# working.net
KiCad netlist of a schematic drawn in EAGLE
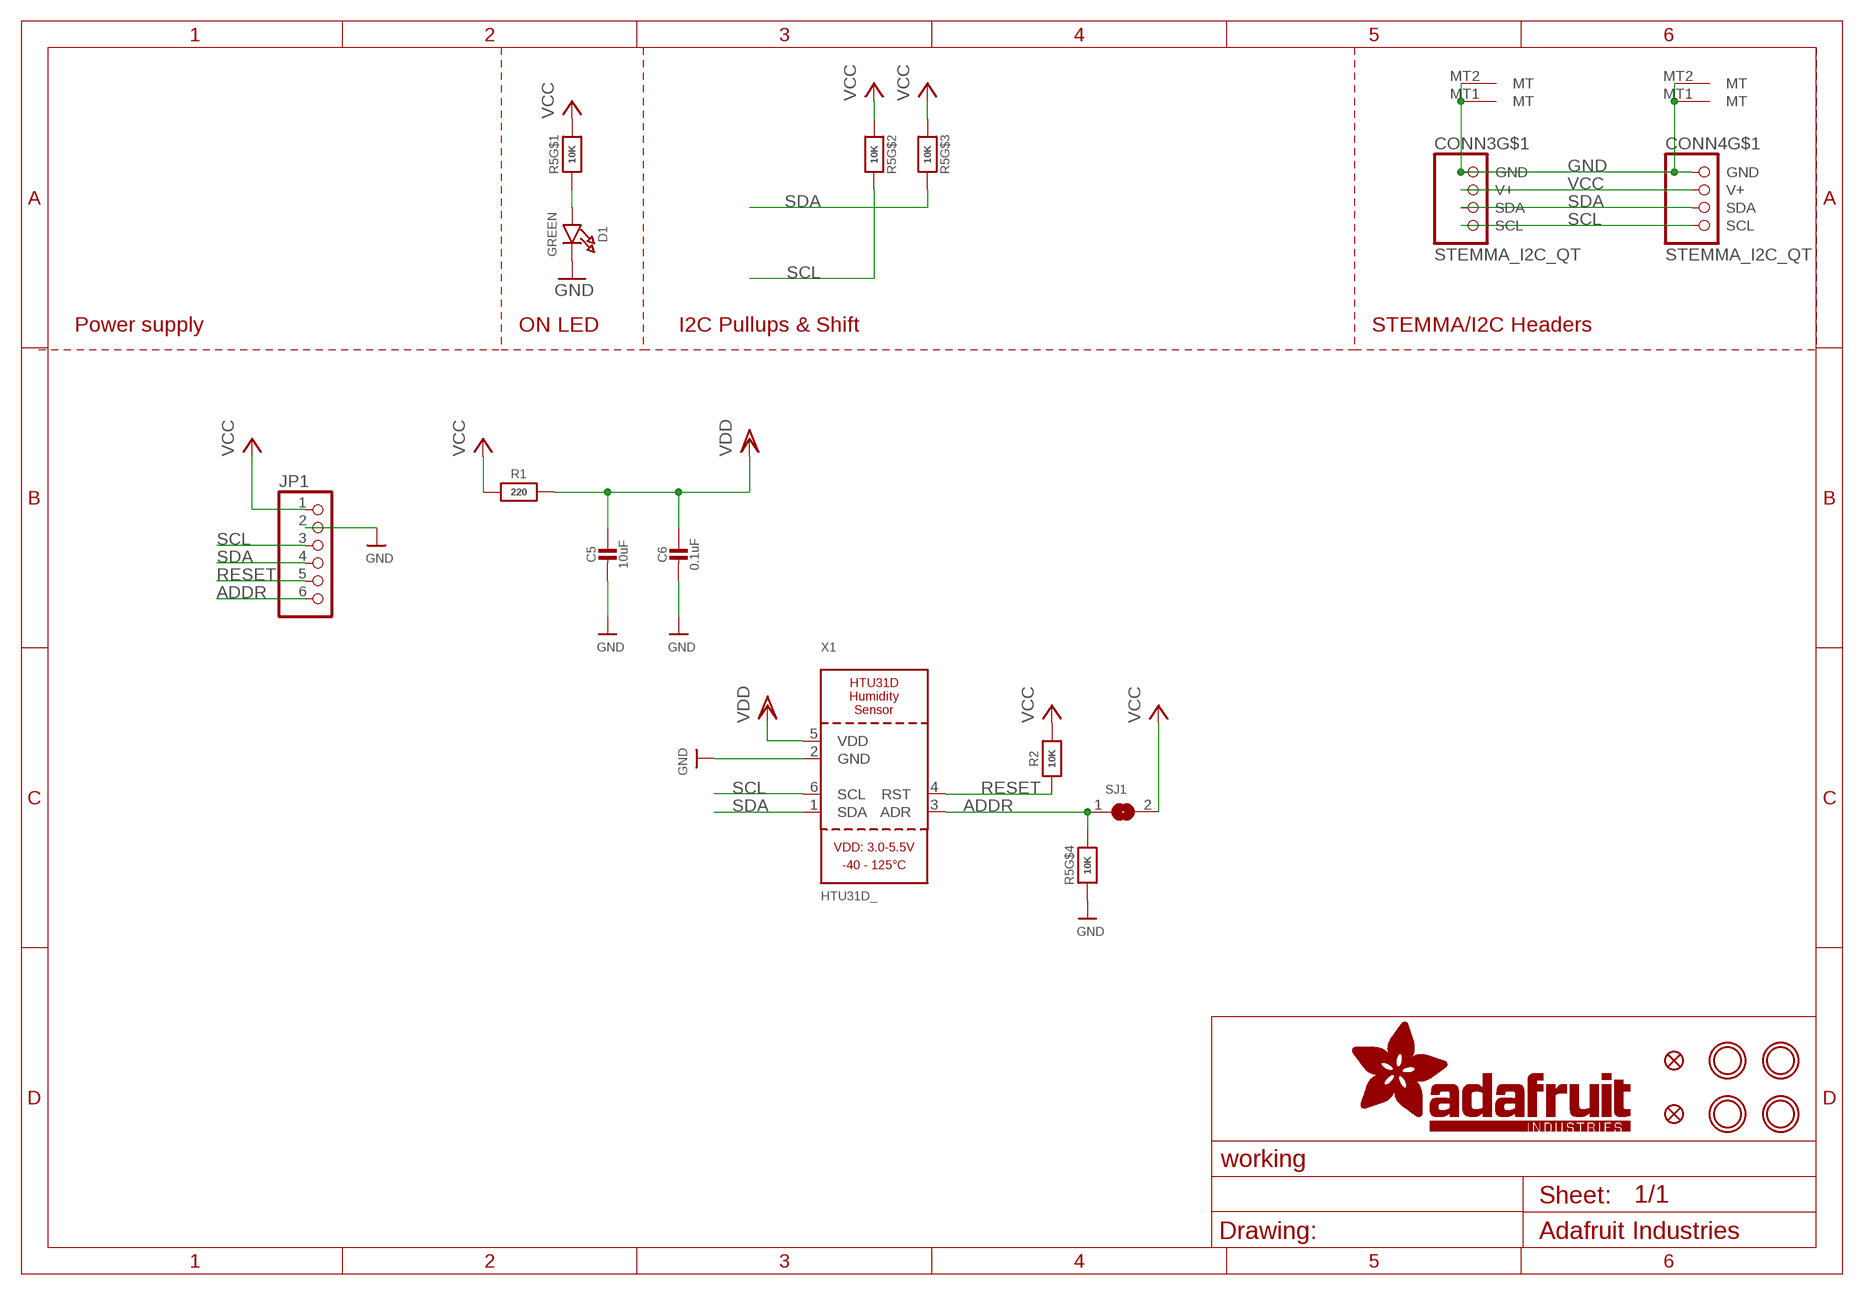
[diagram p0: schematic, sheet 1]

(export (version "E")
  (design (tool "Eeschema 10.0.6"))
  (components
    (comp (ref "C5")
      (value "10uF")
      (footprint "eagle-import:0805-NO")
      (libsource (lib "eagle-import") (part "CAP_CERAMIC0805-NOOUTLINE"))
    )
    (comp (ref "C6")
      (value "0.1uF")
      (footprint "eagle-import:0603-NO")
      (libsource (lib "eagle-import") (part "CAP_CERAMIC0603_NO"))
    )
    (comp (ref "CONN3")
      (value "STEMMA_I2C_QT")
      (footprint "eagle-import:JST_SH4")
      (libsource (lib "eagle-import") (part "STEMMA_I2C_QT"))
    )
    (comp (ref "CONN4")
      (value "STEMMA_I2C_QT")
      (footprint "eagle-import:JST_SH4")
      (libsource (lib "eagle-import") (part "STEMMA_I2C_QT"))
    )
    (comp (ref "D1")
      (value "GREEN")
      (footprint "eagle-import:CHIPLED_0603_NOOUTLINE")
      (libsource (lib "eagle-import") (part "LED0603_NOOUTLINE"))
    )
    (comp (ref "FID3")
      (value "FIDUCIAL_1MM")
      (footprint "eagle-import:FIDUCIAL_1MM")
      (libsource (lib "eagle-import") (part "FIDUCIAL_1MM"))
    )
    (comp (ref "FID4")
      (value "FIDUCIAL_1MM")
      (footprint "eagle-import:FIDUCIAL_1MM")
      (libsource (lib "eagle-import") (part "FIDUCIAL_1MM"))
    )
    (comp (ref "JP1")
      (value "HEADER-1X670MIL")
      (footprint "eagle-import:1X06_ROUND_70")
      (libsource (lib "eagle-import") (part "HEADER-1X670MIL"))
    )
    (comp (ref "R1")
      (value "220")
      (footprint "eagle-import:0603-NO")
      (libsource (lib "eagle-import") (part "RESISTOR_0603_NOOUT"))
    )
    (comp (ref "R2")
      (value "10K")
      (footprint "eagle-import:0603-NO")
      (libsource (lib "eagle-import") (part "RESISTOR_0603_NOOUT"))
    )
    (comp (ref "R5")
      (value "10K")
      (footprint "eagle-import:RESPACK_4X0603")
      (libsource (lib "eagle-import") (part "RESISTOR_4PACK"))
    )
    (comp (ref "SJ1")
      (value "SOLDERJUMPER")
      (footprint "eagle-import:SOLDERJUMPER_ARROW_NOPASTE")
      (libsource (lib "eagle-import") (part "SOLDERJUMPER"))
    )
    (comp (ref "U$19")
      (value "MOUNTINGHOLE2.5")
      (footprint "eagle-import:MOUNTINGHOLE_2.5_PLATED")
      (libsource (lib "eagle-import") (part "MOUNTINGHOLE2.5"))
    )
    (comp (ref "U$20")
      (value "MOUNTINGHOLE2.5")
      (footprint "eagle-import:MOUNTINGHOLE_2.5_PLATED")
      (libsource (lib "eagle-import") (part "MOUNTINGHOLE2.5"))
    )
    (comp (ref "U$22")
      (value "MOUNTINGHOLE2.5")
      (footprint "eagle-import:MOUNTINGHOLE_2.5_PLATED")
      (libsource (lib "eagle-import") (part "MOUNTINGHOLE2.5"))
    )
    (comp (ref "U$25")
      (value "MOUNTINGHOLE2.5")
      (footprint "eagle-import:MOUNTINGHOLE_2.5_PLATED")
      (libsource (lib "eagle-import") (part "MOUNTINGHOLE2.5"))
    )
    (comp (ref "X1")
      (value "HTU31D_")
      (footprint "eagle-import:HTU31D")
      (libsource (lib "eagle-import") (part "HTU31D_"))
    )
  )
  (nets
    (net (code "1") (name "/ADDR") (class "Default")
      (node (ref "JP1") (pin "6") (pinfunction "6_6") (pintype "passive"))
      (node (ref "R5") (pin "5") (pinfunction "2_5") (pintype "passive"))
      (node (ref "SJ1") (pin "1") (pinfunction "1_1") (pintype "passive"))
      (node (ref "X1") (pin "3") (pinfunction "ADR_3") (pintype "input"))
    )
    (net (code "2") (name "/RESET") (class "Default")
      (node (ref "JP1") (pin "5") (pinfunction "5_5") (pintype "passive"))
      (node (ref "R2") (pin "1") (pinfunction "1_1") (pintype "passive"))
      (node (ref "X1") (pin "4") (pinfunction "RST_4") (pintype "input"))
    )
    (net (code "3") (name "/SCL") (class "Default")
      (node (ref "CONN3") (pin "4") (pinfunction "SCL_4") (pintype "passive"))
      (node (ref "CONN4") (pin "4") (pinfunction "SCL_4") (pintype "passive"))
      (node (ref "JP1") (pin "3") (pinfunction "3_3") (pintype "passive"))
      (node (ref "R5") (pin "7") (pinfunction "2_7") (pintype "passive"))
      (node (ref "X1") (pin "6") (pinfunction "SCL_6") (pintype "input"))
    )
    (net (code "4") (name "/SDA") (class "Default")
      (node (ref "CONN3") (pin "3") (pinfunction "SDA_3") (pintype "passive"))
      (node (ref "CONN4") (pin "3") (pinfunction "SDA_3") (pintype "passive"))
      (node (ref "JP1") (pin "4") (pinfunction "4_4") (pintype "passive"))
      (node (ref "R5") (pin "6") (pinfunction "2_6") (pintype "passive"))
      (node (ref "X1") (pin "1") (pinfunction "SDA_1") (pintype "bidirectional"))
    )
    (net (code "5") (name "GND") (class "Default")
      (node (ref "C5") (pin "2") (pinfunction "2_2") (pintype "passive"))
      (node (ref "C6") (pin "2") (pinfunction "2_2") (pintype "passive"))
      (node (ref "CONN3") (pin "1") (pinfunction "GND_1") (pintype "passive"))
      (node (ref "CONN3") (pin "MT1") (pinfunction "MT_MT1") (pintype "bidirectional"))
      (node (ref "CONN3") (pin "MT2") (pinfunction "MT_MT2") (pintype "bidirectional"))
      (node (ref "CONN4") (pin "1") (pinfunction "GND_1") (pintype "passive"))
      (node (ref "CONN4") (pin "MT1") (pinfunction "MT_MT1") (pintype "bidirectional"))
      (node (ref "CONN4") (pin "MT2") (pinfunction "MT_MT2") (pintype "bidirectional"))
      (node (ref "D1") (pin "C") (pinfunction "C_C") (pintype "passive"))
      (node (ref "JP1") (pin "2") (pinfunction "2_2") (pintype "passive"))
      (node (ref "R5") (pin "4") (pinfunction "1_4") (pintype "passive"))
      (node (ref "X1") (pin "2") (pinfunction "GND_2") (pintype "power_in"))
    )
    (net (code "6") (name "Net-(D1-PadA)") (class "Default")
      (node (ref "D1") (pin "A") (pinfunction "A_A") (pintype "passive"))
      (node (ref "R5") (pin "1") (pinfunction "1_1") (pintype "passive"))
    )
    (net (code "7") (name "VCC") (class "Default")
      (node (ref "CONN3") (pin "2") (pinfunction "V+_2") (pintype "passive"))
      (node (ref "CONN4") (pin "2") (pinfunction "V+_2") (pintype "passive"))
      (node (ref "JP1") (pin "1") (pinfunction "1_1") (pintype "passive"))
      (node (ref "R1") (pin "1") (pinfunction "1_1") (pintype "passive"))
      (node (ref "R2") (pin "2") (pinfunction "2_2") (pintype "passive"))
      (node (ref "R5") (pin "2") (pinfunction "1_2") (pintype "passive"))
      (node (ref "R5") (pin "3") (pinfunction "1_3") (pintype "passive"))
      (node (ref "R5") (pin "8") (pinfunction "2_8") (pintype "passive"))
      (node (ref "SJ1") (pin "2") (pinfunction "2_2") (pintype "passive"))
    )
    (net (code "8") (name "VDD") (class "Default")
      (node (ref "C5") (pin "1") (pinfunction "1_1") (pintype "passive"))
      (node (ref "C6") (pin "1") (pinfunction "1_1") (pintype "passive"))
      (node (ref "R1") (pin "2") (pinfunction "2_2") (pintype "passive"))
      (node (ref "X1") (pin "5") (pinfunction "VDD_5") (pintype "power_in"))
    )
  )
)
